# AVCC_3.net
KiCad netlist of a schematic drawn in Altium Designer
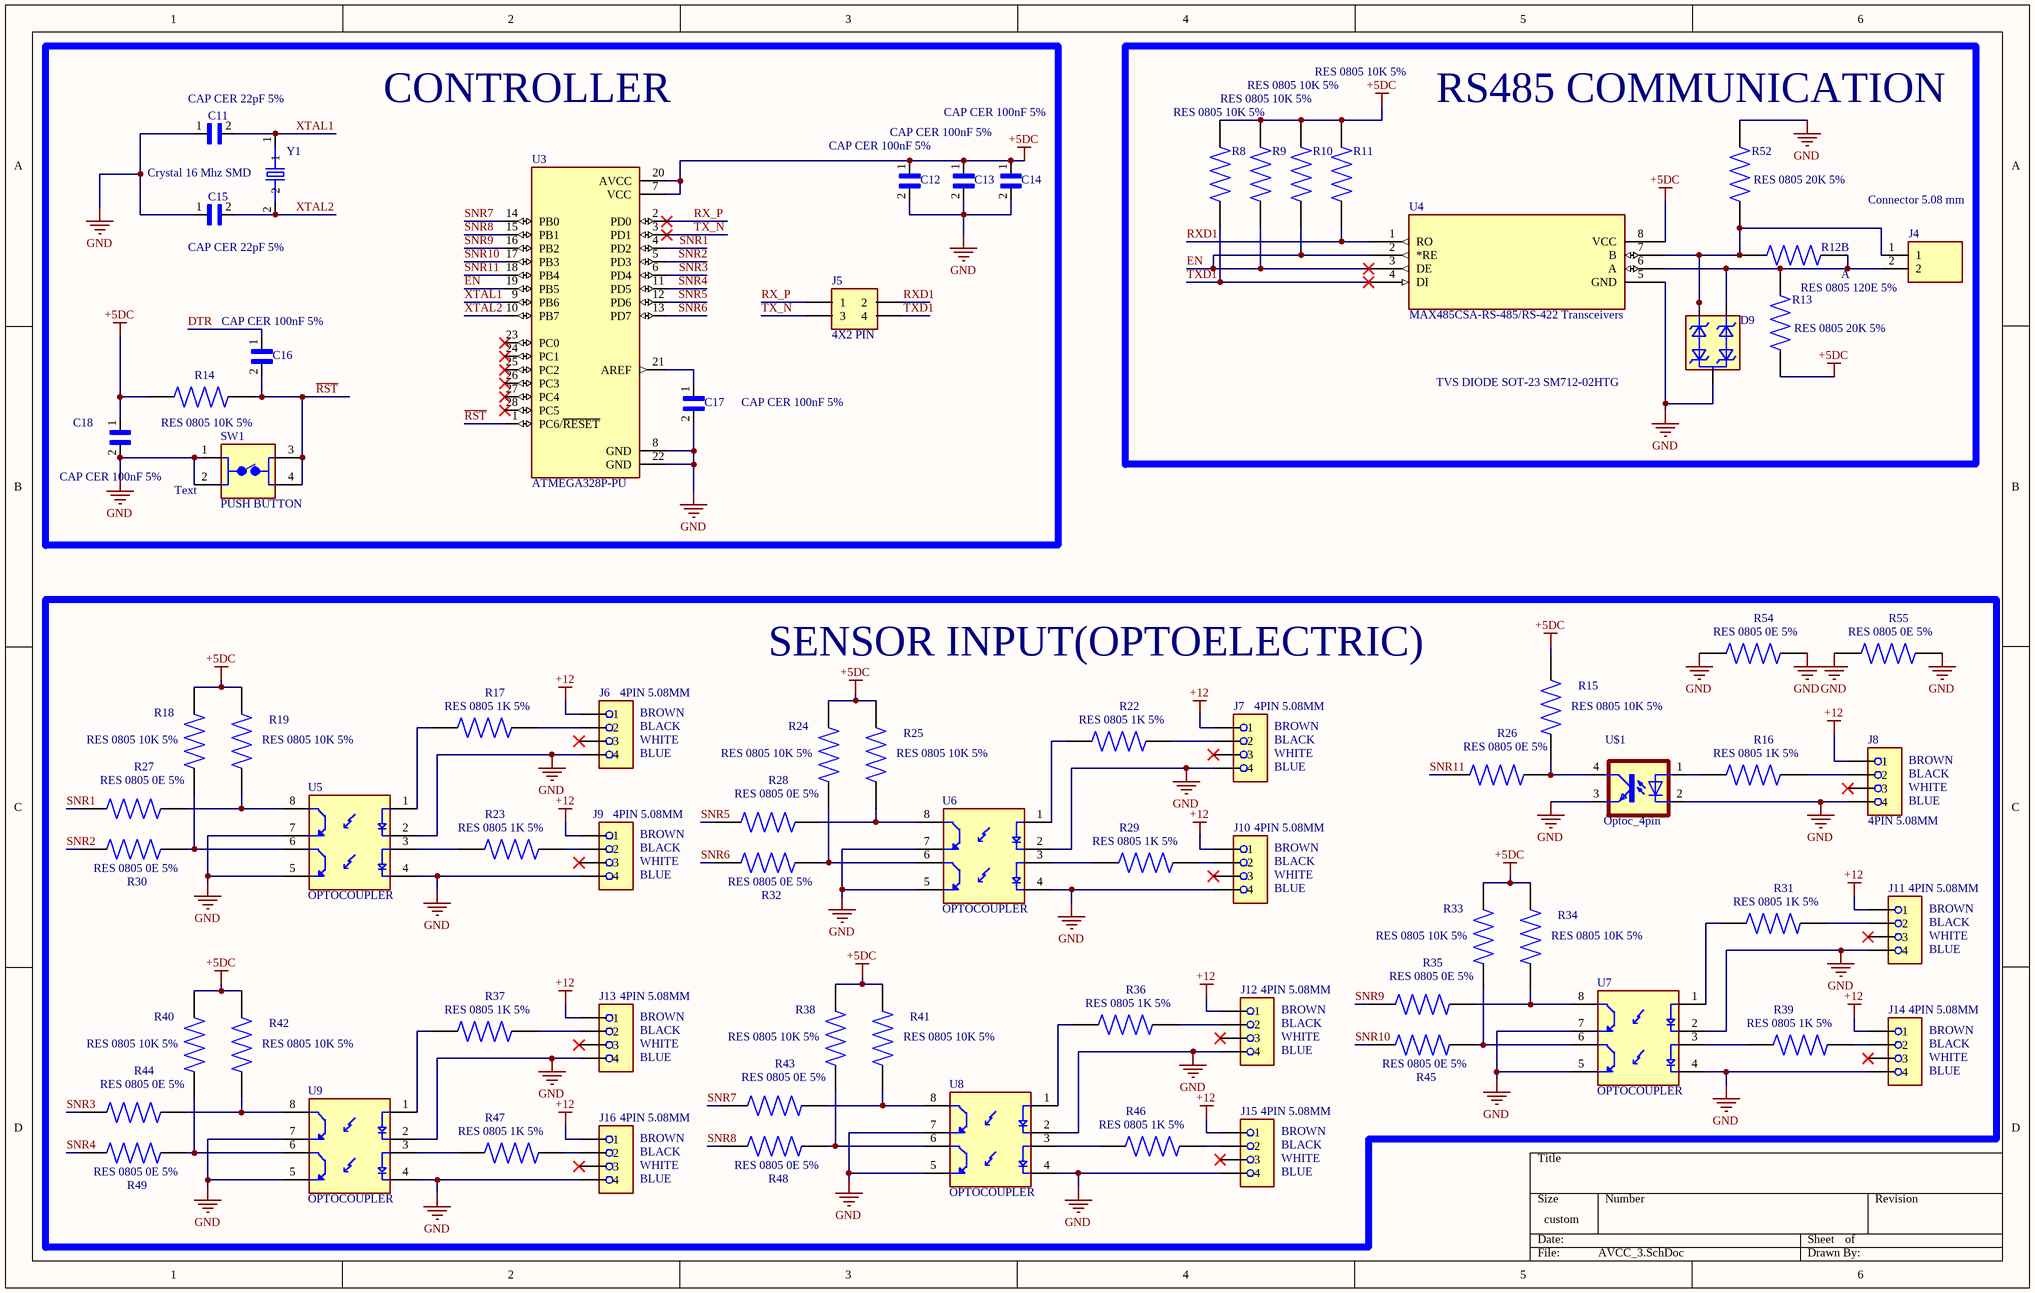
[diagram p0: AVCC_3.SchDoc]

(export (version "E")
  (design (tool "Eeschema 10.0.6"))
  (components
    (comp (ref "C11")
      (value "CAP CER 22pF 5%")
      (footprint "CAP CER 100pF 5%")
      (description "CAP CER 100PF50V X7R 0805")
      (fields (field (name "MP") "GCJ216R71H222KA01D"))
      (libsource (lib "") (part "CAP CER 100pF 5%_1"))
    )
    (comp (ref "C12")
      (value "CAP CER 100nF 5%")
      (footprint "CAP CER 100pF 5%")
      (description "CAP CER 100PF50V X7R 0805")
      (fields (field (name "MP") "GCJ216R71H222KA01D"))
      (libsource (lib "RS485_SCH_Lib") (part "CAP CER 100pF 5%"))
    )
    (comp (ref "C13")
      (value "CAP CER 100nF 5%")
      (footprint "CAP CER 100pF 5%")
      (description "CAP CER 100PF50V X7R 0805")
      (fields (field (name "MP") "GCJ216R71H222KA01D"))
      (libsource (lib "RS485_SCH_Lib") (part "CAP CER 100pF 5%"))
    )
    (comp (ref "C14")
      (value "CAP CER 100nF 5%")
      (footprint "CAP CER 100pF 5%")
      (description "CAP CER 100PF50V X7R 0805")
      (fields (field (name "MP") "GCJ216R71H222KA01D"))
      (libsource (lib "RS485_SCH_Lib") (part "CAP CER 100pF 5%"))
    )
    (comp (ref "C15")
      (value "CAP CER 22pF 5%")
      (footprint "CAP CER 100pF 5%")
      (description "CAP CER 100PF50V X7R 0805")
      (fields (field (name "MP") "GCJ216R71H222KA01D"))
      (libsource (lib "") (part "CAP CER 100pF 5%_1"))
    )
    (comp (ref "C16")
      (value "CAP CER 100nF 5%")
      (footprint "CAP CER 100pF 5%")
      (description "CAP CER 100PF50V X7R 0805")
      (fields (field (name "MP") "GCJ216R71H222KA01D"))
      (libsource (lib "RS485_SCH_Lib") (part "CAP CER 100pF 5%"))
    )
    (comp (ref "C17")
      (value "CAP CER 100nF 5%")
      (footprint "CAP CER 100pF 5%")
      (description "CAP CER 100PF50V X7R 0805")
      (fields (field (name "MP") "GCJ216R71H222KA01D"))
      (libsource (lib "RS485_SCH_Lib") (part "CAP CER 100pF 5%"))
    )
    (comp (ref "C18")
      (value "CAP CER 100nF 5%")
      (footprint "CAP CER 100pF 5%")
      (description "CAP CER 100PF50V X7R 0805")
      (fields (field (name "MP") "GCJ216R71H222KA01D"))
      (libsource (lib "RS485_SCH_Lib") (part "CAP CER 100pF 5%"))
    )
    (comp (ref "D9")
      (value "TVS DIODE SOT-23 SM712-02HTG")
      (footprint "TVS Diode SOT23")
      (fields (field (name "MF") "Littelfuse Inc.") (field (name "MP") "SM712-02HTG"))
      (libsource (lib "RS485_SCH_Lib") (part "TVS DIODE SOT-23 SM712-02HTG"))
    )
    (comp (ref "J4")
      (value "Connector 5.08 mm")
      (footprint "Connector 5.08 mm")
      (description "MOLEX,Screw Type, Horizontal, 5.08 Pitch, 24~12 (AWG), Terminal Block Connector")
      (fields (field (name "MF") "Same Sky") (field (name "MP") "TB007-508-02BE"))
      (libsource (lib "RS485_SCH_Lib") (part "Connector 5.08 mm"))
    )
    (comp (ref "J5")
      (value "4X2 PIN")
      (footprint "4PIN BURGE")
      (description "Connector Header Through Hole 4 position 0.100 (2.54mm), 4X2 PIN")
      (fields (field (name "MF") "Samtec") (field (name "MP") "MTLW-102-05-G-D-180"))
      (libsource (lib "RS485_SCH_Lib") (part "4PIN BURGE"))
    )
    (comp (ref "J6")
      (value "4PIN 5.08MM")
      (footprint "TERMINSL SCREW")
      (description "TERMINSL SCREW, 4PIN, 5.08MM")
      (fields (field (name "MF") "{'manufacturer': u'Phoenix Contact'}") (field (name "MP") "1995664"))
      (libsource (lib "RS485_SCH_Lib") (part "TERMINSL SCREW"))
    )
    (comp (ref "J7")
      (value "4PIN 5.08MM")
      (footprint "TERMINSL SCREW")
      (description "TERMINSL SCREW, 4PIN, 5.08MM")
      (fields (field (name "MF") "{'manufacturer': u'Phoenix Contact'}") (field (name "MP") "1995664"))
      (libsource (lib "RS485_SCH_Lib") (part "TERMINSL SCREW"))
    )
    (comp (ref "J8")
      (value "4PIN 5.08MM")
      (footprint "TERMINSL SCREW")
      (description "TERMINSL SCREW, 4PIN, 5.08MM")
      (fields (field (name "MF") "{'manufacturer': u'Phoenix Contact'}") (field (name "MP") "1995664"))
      (libsource (lib "RS485_SCH_Lib") (part "TERMINSL SCREW"))
    )
    (comp (ref "J9")
      (value "4PIN 5.08MM")
      (footprint "TERMINSL SCREW")
      (description "TERMINSL SCREW, 4PIN, 5.08MM")
      (fields (field (name "MF") "{'manufacturer': u'Phoenix Contact'}") (field (name "MP") "1995664"))
      (libsource (lib "RS485_SCH_Lib") (part "TERMINSL SCREW"))
    )
    (comp (ref "J10")
      (value "4PIN 5.08MM")
      (footprint "TERMINSL SCREW")
      (description "TERMINSL SCREW, 4PIN, 5.08MM")
      (fields (field (name "MF") "{'manufacturer': u'Phoenix Contact'}") (field (name "MP") "1995664"))
      (libsource (lib "RS485_SCH_Lib") (part "TERMINSL SCREW"))
    )
    (comp (ref "J11")
      (value "4PIN 5.08MM")
      (footprint "TERMINSL SCREW")
      (description "TERMINSL SCREW, 4PIN, 5.08MM")
      (fields (field (name "MF") "{'manufacturer': u'Phoenix Contact'}") (field (name "MP") "1995664"))
      (libsource (lib "RS485_SCH_Lib") (part "TERMINSL SCREW"))
    )
    (comp (ref "J12")
      (value "4PIN 5.08MM")
      (footprint "TERMINSL SCREW")
      (description "TERMINSL SCREW, 4PIN, 5.08MM")
      (fields (field (name "MF") "{'manufacturer': u'Phoenix Contact'}") (field (name "MP") "1995664"))
      (libsource (lib "RS485_SCH_Lib") (part "TERMINSL SCREW"))
    )
    (comp (ref "J13")
      (value "4PIN 5.08MM")
      (footprint "TERMINSL SCREW")
      (description "TERMINSL SCREW, 4PIN, 5.08MM")
      (fields (field (name "MF") "{'manufacturer': u'Phoenix Contact'}") (field (name "MP") "1995664"))
      (libsource (lib "RS485_SCH_Lib") (part "TERMINSL SCREW"))
    )
    (comp (ref "J14")
      (value "4PIN 5.08MM")
      (footprint "TERMINSL SCREW")
      (description "TERMINSL SCREW, 4PIN, 5.08MM")
      (fields (field (name "MF") "{'manufacturer': u'Phoenix Contact'}") (field (name "MP") "1995664"))
      (libsource (lib "RS485_SCH_Lib") (part "TERMINSL SCREW"))
    )
    (comp (ref "J15")
      (value "4PIN 5.08MM")
      (footprint "TERMINSL SCREW")
      (description "TERMINSL SCREW, 4PIN, 5.08MM")
      (fields (field (name "MF") "{'manufacturer': u'Phoenix Contact'}") (field (name "MP") "1995664"))
      (libsource (lib "RS485_SCH_Lib") (part "TERMINSL SCREW"))
    )
    (comp (ref "J16")
      (value "4PIN 5.08MM")
      (footprint "TERMINSL SCREW")
      (description "TERMINSL SCREW, 4PIN, 5.08MM")
      (fields (field (name "MF") "{'manufacturer': u'Phoenix Contact'}") (field (name "MP") "1995664"))
      (libsource (lib "RS485_SCH_Lib") (part "TERMINSL SCREW"))
    )
    (comp (ref "R8")
      (value "RES 0805 10K 5%")
      (footprint "RES 0805 10K 5%")
      (fields (field (name "MP") "ERJ-6GEYJ103V") (field (name "MF") "Panasonic Electronic"))
      (libsource (lib "RS485_SCH_Lib") (part "RES 0805 10K 5%"))
    )
    (comp (ref "R9")
      (value "RES 0805 10K 5%")
      (footprint "RES 0805 10K 5%")
      (fields (field (name "MP") "ERJ-6GEYJ103V") (field (name "MF") "Panasonic Electronic"))
      (libsource (lib "RS485_SCH_Lib") (part "RES 0805 10K 5%"))
    )
    (comp (ref "R10")
      (value "RES 0805 10K 5%")
      (footprint "RES 0805 10K 5%")
      (fields (field (name "MP") "ERJ-6GEYJ103V") (field (name "MF") "Panasonic Electronic"))
      (libsource (lib "RS485_SCH_Lib") (part "RES 0805 10K 5%"))
    )
    (comp (ref "R11")
      (value "RES 0805 10K 5%")
      (footprint "RES 0805 10K 5%")
      (fields (field (name "MP") "ERJ-6GEYJ103V") (field (name "MF") "Panasonic Electronic"))
      (libsource (lib "RS485_SCH_Lib") (part "RES 0805 10K 5%"))
    )
    (comp (ref "R12")
      (value "RES 0805 120E 5%")
      (footprint "RES 0805 10K 5%")
      (fields (field (name "MP") "ERJ-6GEYJ103V") (field (name "MF") "Panasonic Electronic"))
      (libsource (lib "RS485_SCH_Lib") (part "RES 0805 10K 5%"))
    )
    (comp (ref "R13")
      (value "RES 0805 20K 5%")
      (footprint "RES 0805 10K 5%")
      (fields (field (name "MP") "ERJ-6GEYJ103V") (field (name "MF") "Panasonic Electronic"))
      (libsource (lib "RS485_SCH_Lib") (part "RES 0805 10K 5%"))
    )
    (comp (ref "R14")
      (value "RES 0805 10K 5%")
      (footprint "RES 0805 10K 5%")
      (fields (field (name "MP") "ERJ-6GEYJ103V") (field (name "MF") "Panasonic Electronic"))
      (libsource (lib "RS485_SCH_Lib") (part "RES 0805 10K 5%"))
    )
    (comp (ref "R15")
      (value "RES 0805 10K 5%")
      (footprint "RES 0805 10K 5%")
      (fields (field (name "MP") "ERJ-6GEYJ103V") (field (name "MF") "Panasonic Electronic"))
      (libsource (lib "RS485_SCH_Lib") (part "RES 0805 10K 5%"))
    )
    (comp (ref "R16")
      (value "RES 0805 1K 5%")
      (footprint "RES 0805 10K 5%")
      (fields (field (name "MP") "ERJ-6GEYJ103V") (field (name "MF") "Panasonic Electronic"))
      (libsource (lib "RS485_SCH_Lib") (part "RES 0805 10K 5%"))
    )
    (comp (ref "R17")
      (value "RES 0805 1K 5%")
      (footprint "RES 0805 10K 5%")
      (fields (field (name "MP") "ERJ-6GEYJ103V") (field (name "MF") "Panasonic Electronic"))
      (libsource (lib "RS485_SCH_Lib") (part "RES 0805 10K 5%"))
    )
    (comp (ref "R18")
      (value "RES 0805 10K 5%")
      (footprint "RES 0805 10K 5%")
      (fields (field (name "MP") "ERJ-6GEYJ103V") (field (name "MF") "Panasonic Electronic"))
      (libsource (lib "RS485_SCH_Lib") (part "RES 0805 10K 5%"))
    )
    (comp (ref "R19")
      (value "RES 0805 10K 5%")
      (footprint "RES 0805 10K 5%")
      (fields (field (name "MP") "ERJ-6GEYJ103V") (field (name "MF") "Panasonic Electronic"))
      (libsource (lib "RS485_SCH_Lib") (part "RES 0805 10K 5%"))
    )
    (comp (ref "R22")
      (value "RES 0805 1K 5%")
      (footprint "RES 0805 10K 5%")
      (fields (field (name "MP") "ERJ-6GEYJ103V") (field (name "MF") "Panasonic Electronic"))
      (libsource (lib "RS485_SCH_Lib") (part "RES 0805 10K 5%"))
    )
    (comp (ref "R23")
      (value "RES 0805 1K 5%")
      (footprint "RES 0805 10K 5%")
      (fields (field (name "MP") "ERJ-6GEYJ103V") (field (name "MF") "Panasonic Electronic"))
      (libsource (lib "RS485_SCH_Lib") (part "RES 0805 10K 5%"))
    )
    (comp (ref "R24")
      (value "RES 0805 10K 5%")
      (footprint "RES 0805 10K 5%")
      (fields (field (name "MP") "ERJ-6GEYJ103V") (field (name "MF") "Panasonic Electronic"))
      (libsource (lib "RS485_SCH_Lib") (part "RES 0805 10K 5%"))
    )
    (comp (ref "R25")
      (value "RES 0805 10K 5%")
      (footprint "RES 0805 10K 5%")
      (fields (field (name "MP") "ERJ-6GEYJ103V") (field (name "MF") "Panasonic Electronic"))
      (libsource (lib "RS485_SCH_Lib") (part "RES 0805 10K 5%"))
    )
    (comp (ref "R26")
      (value "RES 0805 0E 5%")
      (footprint "RES 0805 10K 5%")
      (fields (field (name "MP") "ERJ-6GEYJ103V") (field (name "MF") "Panasonic Electronic"))
      (libsource (lib "RS485_SCH_Lib") (part "RES 0805 10K 5%"))
    )
    (comp (ref "R27")
      (value "RES 0805 0E 5%")
      (footprint "RES 0805 10K 5%")
      (fields (field (name "MP") "ERJ-6GEYJ103V") (field (name "MF") "Panasonic Electronic"))
      (libsource (lib "RS485_SCH_Lib") (part "RES 0805 10K 5%"))
    )
    (comp (ref "R28")
      (value "RES 0805 0E 5%")
      (footprint "RES 0805 10K 5%")
      (fields (field (name "MP") "ERJ-6GEYJ103V") (field (name "MF") "Panasonic Electronic"))
      (libsource (lib "RS485_SCH_Lib") (part "RES 0805 10K 5%"))
    )
    (comp (ref "R29")
      (value "RES 0805 1K 5%")
      (footprint "RES 0805 10K 5%")
      (fields (field (name "MP") "ERJ-6GEYJ103V") (field (name "MF") "Panasonic Electronic"))
      (libsource (lib "RS485_SCH_Lib") (part "RES 0805 10K 5%"))
    )
    (comp (ref "R30")
      (value "RES 0805 0E 5%")
      (footprint "RES 0805 10K 5%")
      (fields (field (name "MP") "ERJ-6GEYJ103V") (field (name "MF") "Panasonic Electronic"))
      (libsource (lib "RS485_SCH_Lib") (part "RES 0805 10K 5%"))
    )
    (comp (ref "R31")
      (value "RES 0805 1K 5%")
      (footprint "RES 0805 10K 5%")
      (fields (field (name "MP") "ERJ-6GEYJ103V") (field (name "MF") "Panasonic Electronic"))
      (libsource (lib "RS485_SCH_Lib") (part "RES 0805 10K 5%"))
    )
    (comp (ref "R32")
      (value "RES 0805 0E 5%")
      (footprint "RES 0805 10K 5%")
      (fields (field (name "MP") "ERJ-6GEYJ103V") (field (name "MF") "Panasonic Electronic"))
      (libsource (lib "RS485_SCH_Lib") (part "RES 0805 10K 5%"))
    )
    (comp (ref "R33")
      (value "RES 0805 10K 5%")
      (footprint "RES 0805 10K 5%")
      (fields (field (name "MP") "ERJ-6GEYJ103V") (field (name "MF") "Panasonic Electronic"))
      (libsource (lib "RS485_SCH_Lib") (part "RES 0805 10K 5%"))
    )
    (comp (ref "R34")
      (value "RES 0805 10K 5%")
      (footprint "RES 0805 10K 5%")
      (fields (field (name "MP") "ERJ-6GEYJ103V") (field (name "MF") "Panasonic Electronic"))
      (libsource (lib "RS485_SCH_Lib") (part "RES 0805 10K 5%"))
    )
    (comp (ref "R35")
      (value "RES 0805 0E 5%")
      (footprint "RES 0805 10K 5%")
      (fields (field (name "MP") "ERJ-6GEYJ103V") (field (name "MF") "Panasonic Electronic"))
      (libsource (lib "RS485_SCH_Lib") (part "RES 0805 10K 5%"))
    )
    (comp (ref "R36")
      (value "RES 0805 1K 5%")
      (footprint "RES 0805 10K 5%")
      (fields (field (name "MP") "ERJ-6GEYJ103V") (field (name "MF") "Panasonic Electronic"))
      (libsource (lib "RS485_SCH_Lib") (part "RES 0805 10K 5%"))
    )
    (comp (ref "R37")
      (value "RES 0805 1K 5%")
      (footprint "RES 0805 10K 5%")
      (fields (field (name "MP") "ERJ-6GEYJ103V") (field (name "MF") "Panasonic Electronic"))
      (libsource (lib "RS485_SCH_Lib") (part "RES 0805 10K 5%"))
    )
    (comp (ref "R38")
      (value "RES 0805 10K 5%")
      (footprint "RES 0805 10K 5%")
      (fields (field (name "MP") "ERJ-6GEYJ103V") (field (name "MF") "Panasonic Electronic"))
      (libsource (lib "RS485_SCH_Lib") (part "RES 0805 10K 5%"))
    )
    (comp (ref "R39")
      (value "RES 0805 1K 5%")
      (footprint "RES 0805 10K 5%")
      (fields (field (name "MP") "ERJ-6GEYJ103V") (field (name "MF") "Panasonic Electronic"))
      (libsource (lib "RS485_SCH_Lib") (part "RES 0805 10K 5%"))
    )
    (comp (ref "R40")
      (value "RES 0805 10K 5%")
      (footprint "RES 0805 10K 5%")
      (fields (field (name "MP") "ERJ-6GEYJ103V") (field (name "MF") "Panasonic Electronic"))
      (libsource (lib "RS485_SCH_Lib") (part "RES 0805 10K 5%"))
    )
    (comp (ref "R41")
      (value "RES 0805 10K 5%")
      (footprint "RES 0805 10K 5%")
      (fields (field (name "MP") "ERJ-6GEYJ103V") (field (name "MF") "Panasonic Electronic"))
      (libsource (lib "RS485_SCH_Lib") (part "RES 0805 10K 5%"))
    )
    (comp (ref "R42")
      (value "RES 0805 10K 5%")
      (footprint "RES 0805 10K 5%")
      (fields (field (name "MP") "ERJ-6GEYJ103V") (field (name "MF") "Panasonic Electronic"))
      (libsource (lib "RS485_SCH_Lib") (part "RES 0805 10K 5%"))
    )
    (comp (ref "R43")
      (value "RES 0805 0E 5%")
      (footprint "RES 0805 10K 5%")
      (fields (field (name "MP") "ERJ-6GEYJ103V") (field (name "MF") "Panasonic Electronic"))
      (libsource (lib "RS485_SCH_Lib") (part "RES 0805 10K 5%"))
    )
    (comp (ref "R44")
      (value "RES 0805 0E 5%")
      (footprint "RES 0805 10K 5%")
      (fields (field (name "MP") "ERJ-6GEYJ103V") (field (name "MF") "Panasonic Electronic"))
      (libsource (lib "RS485_SCH_Lib") (part "RES 0805 10K 5%"))
    )
    (comp (ref "R45")
      (value "RES 0805 0E 5%")
      (footprint "RES 0805 10K 5%")
      (fields (field (name "MP") "ERJ-6GEYJ103V") (field (name "MF") "Panasonic Electronic"))
      (libsource (lib "RS485_SCH_Lib") (part "RES 0805 10K 5%"))
    )
    (comp (ref "R46")
      (value "RES 0805 1K 5%")
      (footprint "RES 0805 10K 5%")
      (fields (field (name "MP") "ERJ-6GEYJ103V") (field (name "MF") "Panasonic Electronic"))
      (libsource (lib "RS485_SCH_Lib") (part "RES 0805 10K 5%"))
    )
    (comp (ref "R47")
      (value "RES 0805 1K 5%")
      (footprint "RES 0805 10K 5%")
      (fields (field (name "MP") "ERJ-6GEYJ103V") (field (name "MF") "Panasonic Electronic"))
      (libsource (lib "RS485_SCH_Lib") (part "RES 0805 10K 5%"))
    )
    (comp (ref "R48")
      (value "RES 0805 0E 5%")
      (footprint "RES 0805 10K 5%")
      (fields (field (name "MP") "ERJ-6GEYJ103V") (field (name "MF") "Panasonic Electronic"))
      (libsource (lib "RS485_SCH_Lib") (part "RES 0805 10K 5%"))
    )
    (comp (ref "R49")
      (value "RES 0805 0E 5%")
      (footprint "RES 0805 10K 5%")
      (fields (field (name "MP") "ERJ-6GEYJ103V") (field (name "MF") "Panasonic Electronic"))
      (libsource (lib "RS485_SCH_Lib") (part "RES 0805 10K 5%"))
    )
    (comp (ref "R52")
      (value "RES 0805 20K 5%")
      (footprint "RES 0805 10K 5%")
      (fields (field (name "MP") "ERJ-6GEYJ103V") (field (name "MF") "Panasonic Electronic"))
      (libsource (lib "RS485_SCH_Lib") (part "RES 0805 10K 5%"))
    )
    (comp (ref "R54")
      (value "RES 0805 0E 5%")
      (footprint "RES 0805 10K 5%")
      (fields (field (name "MP") "ERJ-6GEYJ103V") (field (name "MF") "Panasonic Electronic"))
      (libsource (lib "RS485_SCH_Lib") (part "RES 0805 10K 5%"))
    )
    (comp (ref "R55")
      (value "RES 0805 0E 5%")
      (footprint "RES 0805 10K 5%")
      (fields (field (name "MP") "ERJ-6GEYJ103V") (field (name "MF") "Panasonic Electronic"))
      (libsource (lib "RS485_SCH_Lib") (part "RES 0805 10K 5%"))
    )
    (comp (ref "SW1")
      (value "PUSH BUTTON")
      (footprint "Push Button")
      (description "Switch Push Button OFF (ON) SPST Round Button 0.05A 24VDC Momentary Contact PC Pins Thru-Hole")
      (fields (field (name "MF") "TE Connectivity") (field (name "MP") "3-1825910-1"))
      (libsource (lib "RS485_SCH_Lib") (part "PUSH BUTTON"))
    )
    (comp (ref "U$1")
      (value "Optoc_4pin")
      (footprint "Optoisolator")
      (description "TLP521-1,Optoisolator Transistor Output 5300Vrms 1 Channel 4-DIP")
      (fields (field (name "MF") "Isocom") (field (name "MP") "TLP521-1"))
      (libsource (lib "RS485_SCH_Lib") (part "Optoc_4pin"))
    )
    (comp (ref "U3")
      (value "ATMEGA328P-PU")
      (footprint "ATMEGA328P DIP28")
      (description "ATmega Series 20 MHz 32 KB Flash 2 KB SRAM 8-Bit Microcontroller - DIP-28")
      (libsource (lib "RS485_SCH_Lib") (part "ATMEGA328P-PU"))
    )
    (comp (ref "U4")
      (value "MAX485CSA-RS-485/RS-422 Transceivers")
      (footprint "MAX485CSA-RS-485/RS-422 Transceivers")
      (description "Low-Power, Slew-Rate-Limited RS-485/RS-422 Transceivers")
      (fields (field (name "MF") "Analog Devices") (field (name "MP") "MAX485CSA+"))
      (libsource (lib "RS485_SCH_Lib") (part "MAX485CSA-RS-485/RS-422 Transceivers"))
    )
    (comp (ref "U5")
      (value "OPTOCOUPLER")
      (footprint "OPTOCOUPLER")
      (description "TLP521-2,Optoisolateur Ã  sortie transistor 5300 Vrms 2 canaux 8 DIP")
      (fields (field (name "MF") "Toshiba") (field (name "MP") "TLP521-2"))
      (libsource (lib "RS485_SCH_Lib") (part "OPTOCOUPLER"))
    )
    (comp (ref "U6")
      (value "OPTOCOUPLER")
      (footprint "OPTOCOUPLER")
      (description "TLP521-2,Optoisolateur Ã  sortie transistor 5300 Vrms 2 canaux 8 DIP")
      (fields (field (name "MF") "Toshiba") (field (name "MP") "TLP521-2"))
      (libsource (lib "RS485_SCH_Lib") (part "OPTOCOUPLER"))
    )
    (comp (ref "U7")
      (value "OPTOCOUPLER")
      (footprint "OPTOCOUPLER")
      (description "TLP521-2,Optoisolateur Ã  sortie transistor 5300 Vrms 2 canaux 8 DIP")
      (fields (field (name "MF") "Toshiba") (field (name "MP") "TLP521-2"))
      (libsource (lib "RS485_SCH_Lib") (part "OPTOCOUPLER"))
    )
    (comp (ref "U8")
      (value "OPTOCOUPLER")
      (footprint "OPTOCOUPLER")
      (description "TLP521-2,Optoisolateur Ã  sortie transistor 5300 Vrms 2 canaux 8 DIP")
      (fields (field (name "MF") "Toshiba") (field (name "MP") "TLP521-2"))
      (libsource (lib "RS485_SCH_Lib") (part "OPTOCOUPLER"))
    )
    (comp (ref "U9")
      (value "OPTOCOUPLER")
      (footprint "OPTOCOUPLER")
      (description "TLP521-2,Optoisolateur Ã  sortie transistor 5300 Vrms 2 canaux 8 DIP")
      (fields (field (name "MF") "Toshiba") (field (name "MP") "TLP521-2"))
      (libsource (lib "RS485_SCH_Lib") (part "OPTOCOUPLER"))
    )
    (comp (ref "Y1")
      (value "Crystal 16 Mhz SMD")
      (footprint "Crystal 16 Mhz SMD")
      (description "16 Mhz Crystal SMD –CSM-4ALX(28ALX) 12.5mmX4.85mmX4mm")
      (fields (field (name "MF") "Fox Electronics") (field (name "MP") "FOXSDLF/128-20"))
      (libsource (lib "RS485_SCH_Lib") (part "Crystal 16 Mhz SMD"))
    )
  )
  (nets
    (net (code "1") (name "+5DC") (class "Default")
      (node (ref "C12") (pin "1") (pinfunction "1_1") (pintype "passive"))
      (node (ref "C13") (pin "1") (pinfunction "1_1") (pintype "passive"))
      (node (ref "C14") (pin "1") (pinfunction "1_1") (pintype "passive"))
      (node (ref "C18") (pin "1") (pinfunction "1_1") (pintype "passive"))
      (node (ref "R10") (pin "2") (pinfunction "2_2") (pintype "passive"))
      (node (ref "R11") (pin "2") (pinfunction "2_2") (pintype "passive"))
      (node (ref "R13") (pin "1") (pinfunction "1_1") (pintype "passive"))
      (node (ref "R14") (pin "1") (pinfunction "1_1") (pintype "passive"))
      (node (ref "R15") (pin "2") (pinfunction "2_2") (pintype "passive"))
      (node (ref "R18") (pin "2") (pinfunction "2_2") (pintype "passive"))
      (node (ref "R19") (pin "2") (pinfunction "2_2") (pintype "passive"))
      (node (ref "R24") (pin "2") (pinfunction "2_2") (pintype "passive"))
      (node (ref "R25") (pin "2") (pinfunction "2_2") (pintype "passive"))
      (node (ref "R33") (pin "2") (pinfunction "2_2") (pintype "passive"))
      (node (ref "R34") (pin "2") (pinfunction "2_2") (pintype "passive"))
      (node (ref "R38") (pin "2") (pinfunction "2_2") (pintype "passive"))
      (node (ref "R40") (pin "2") (pinfunction "2_2") (pintype "passive"))
      (node (ref "R41") (pin "2") (pinfunction "2_2") (pintype "passive"))
      (node (ref "R42") (pin "2") (pinfunction "2_2") (pintype "passive"))
      (node (ref "R8") (pin "2") (pinfunction "2_2") (pintype "passive"))
      (node (ref "R9") (pin "2") (pinfunction "2_2") (pintype "passive"))
      (node (ref "U3") (pin "20") (pinfunction "AVCC_20") (pintype "power_in"))
      (node (ref "U3") (pin "7") (pinfunction "VCC_7") (pintype "power_in"))
      (node (ref "U4") (pin "8") (pinfunction "VCC_8") (pintype "power_in"))
    )
    (net (code "2") (name "+12") (class "Default")
      (node (ref "J10") (pin "1") (pinfunction "1_1") (pintype "passive"))
      (node (ref "J11") (pin "1") (pinfunction "1_1") (pintype "passive"))
      (node (ref "J12") (pin "1") (pinfunction "1_1") (pintype "passive"))
      (node (ref "J13") (pin "1") (pinfunction "1_1") (pintype "passive"))
      (node (ref "J14") (pin "1") (pinfunction "1_1") (pintype "passive"))
      (node (ref "J15") (pin "1") (pinfunction "1_1") (pintype "passive"))
      (node (ref "J16") (pin "1") (pinfunction "1_1") (pintype "passive"))
      (node (ref "J6") (pin "1") (pinfunction "1_1") (pintype "passive"))
      (node (ref "J7") (pin "1") (pinfunction "1_1") (pintype "passive"))
      (node (ref "J8") (pin "1") (pinfunction "1_1") (pintype "passive"))
      (node (ref "J9") (pin "1") (pinfunction "1_1") (pintype "passive"))
    )
    (net (code "3") (name "/DTR") (class "Default")
      (node (ref "C16") (pin "1") (pinfunction "1_1") (pintype "passive"))
    )
    (net (code "4") (name "/EN") (class "Default")
      (node (ref "R10") (pin "1") (pinfunction "1_1") (pintype "passive"))
      (node (ref "R9") (pin "1") (pinfunction "1_1") (pintype "passive"))
      (node (ref "U3") (pin "19") (pinfunction "PB5_19") (pintype "bidirectional"))
      (node (ref "U4") (pin "2") (pinfunction "*RE_2") (pintype "output"))
      (node (ref "U4") (pin "3") (pinfunction "DE_3") (pintype "output"))
    )
    (net (code "5") (name "/RXD1") (class "Default")
      (node (ref "J5") (pin "02") (pinfunction "2_02") (pintype "passive"))
      (node (ref "R11") (pin "1") (pinfunction "1_1") (pintype "passive"))
      (node (ref "U4") (pin "1") (pinfunction "RO_1") (pintype "output"))
    )
    (net (code "6") (name "/RX_P") (class "Default")
      (node (ref "J5") (pin "01") (pinfunction "1_01") (pintype "passive"))
      (node (ref "U3") (pin "2") (pinfunction "PD0_2") (pintype "bidirectional"))
    )
    (net (code "7") (name "/SNR1") (class "Default")
      (node (ref "R27") (pin "1") (pinfunction "1_1") (pintype "passive"))
      (node (ref "U3") (pin "4") (pinfunction "PD2_4") (pintype "bidirectional"))
    )
    (net (code "8") (name "/SNR2") (class "Default")
      (node (ref "R30") (pin "1") (pinfunction "1_1") (pintype "passive"))
      (node (ref "U3") (pin "5") (pinfunction "PD3_5") (pintype "bidirectional"))
    )
    (net (code "9") (name "/SNR3") (class "Default")
      (node (ref "R44") (pin "1") (pinfunction "1_1") (pintype "passive"))
      (node (ref "U3") (pin "6") (pinfunction "PD4_6") (pintype "bidirectional"))
    )
    (net (code "10") (name "/SNR4") (class "Default")
      (node (ref "R49") (pin "1") (pinfunction "1_1") (pintype "passive"))
      (node (ref "U3") (pin "11") (pinfunction "PD5_11") (pintype "bidirectional"))
    )
    (net (code "11") (name "/SNR5") (class "Default")
      (node (ref "R28") (pin "1") (pinfunction "1_1") (pintype "passive"))
      (node (ref "U3") (pin "12") (pinfunction "PD6_12") (pintype "bidirectional"))
    )
    (net (code "12") (name "/SNR6") (class "Default")
      (node (ref "R32") (pin "1") (pinfunction "1_1") (pintype "passive"))
      (node (ref "U3") (pin "13") (pinfunction "PD7_13") (pintype "bidirectional"))
    )
    (net (code "13") (name "/SNR7") (class "Default")
      (node (ref "R43") (pin "1") (pinfunction "1_1") (pintype "passive"))
      (node (ref "U3") (pin "14") (pinfunction "PB0_14") (pintype "bidirectional"))
    )
    (net (code "14") (name "/SNR8") (class "Default")
      (node (ref "R48") (pin "1") (pinfunction "1_1") (pintype "passive"))
      (node (ref "U3") (pin "15") (pinfunction "PB1_15") (pintype "bidirectional"))
    )
    (net (code "15") (name "/SNR9") (class "Default")
      (node (ref "R35") (pin "1") (pinfunction "1_1") (pintype "passive"))
      (node (ref "U3") (pin "16") (pinfunction "PB2_16") (pintype "bidirectional"))
    )
    (net (code "16") (name "/SNR10") (class "Default")
      (node (ref "R45") (pin "1") (pinfunction "1_1") (pintype "passive"))
      (node (ref "U3") (pin "17") (pinfunction "PB3_17") (pintype "bidirectional"))
    )
    (net (code "17") (name "/SNR11") (class "Default")
      (node (ref "R26") (pin "1") (pinfunction "1_1") (pintype "passive"))
      (node (ref "U3") (pin "18") (pinfunction "PB4_18") (pintype "bidirectional"))
    )
    (net (code "18") (name "/TXD1") (class "Default")
      (node (ref "J5") (pin "04") (pinfunction "4_04") (pintype "passive"))
      (node (ref "R8") (pin "1") (pinfunction "1_1") (pintype "passive"))
      (node (ref "U4") (pin "4") (pinfunction "DI_4") (pintype "input"))
    )
    (net (code "19") (name "/TX_N") (class "Default")
      (node (ref "J5") (pin "03") (pinfunction "3_03") (pintype "passive"))
      (node (ref "U3") (pin "3") (pinfunction "PD1_3") (pintype "bidirectional"))
    )
    (net (code "20") (name "/XTAL1") (class "Default")
      (node (ref "C11") (pin "2") (pinfunction "2_2") (pintype "passive"))
      (node (ref "U3") (pin "9") (pinfunction "PB6_9") (pintype "bidirectional"))
      (node (ref "Y1") (pin "1") (pinfunction "1_1") (pintype "passive"))
    )
    (net (code "21") (name "/XTAL2") (class "Default")
      (node (ref "C15") (pin "2") (pinfunction "2_2") (pintype "passive"))
      (node (ref "U3") (pin "10") (pinfunction "PB7_10") (pintype "bidirectional"))
      (node (ref "Y1") (pin "2") (pinfunction "2_2") (pintype "passive"))
    )
    (net (code "22") (name "/~{RST}") (class "Default")
      (node (ref "C16") (pin "2") (pinfunction "2_2") (pintype "passive"))
      (node (ref "R14") (pin "2") (pinfunction "2_2") (pintype "passive"))
      (node (ref "SW1") (pin "3") (pinfunction "3_3") (pintype "passive"))
      (node (ref "SW1") (pin "4") (pinfunction "4_4") (pintype "passive"))
      (node (ref "U3") (pin "1") (pinfunction "PC6/~{RESET}_1") (pintype "bidirectional"))
    )
    (net (code "23") (name "GND") (class "Default")
      (node (ref "C11") (pin "1") (pinfunction "1_1") (pintype "passive"))
      (node (ref "C12") (pin "2") (pinfunction "2_2") (pintype "passive"))
      (node (ref "C13") (pin "2") (pinfunction "2_2") (pintype "passive"))
      (node (ref "C14") (pin "2") (pinfunction "2_2") (pintype "passive"))
      (node (ref "C15") (pin "1") (pinfunction "1_1") (pintype "passive"))
      (node (ref "C17") (pin "2") (pinfunction "2_2") (pintype "passive"))
      (node (ref "C18") (pin "2") (pinfunction "2_2") (pintype "passive"))
      (node (ref "D9") (pin "3") (pinfunction "3_3") (pintype "passive"))
      (node (ref "J10") (pin "4") (pinfunction "4_4") (pintype "passive"))
      (node (ref "J11") (pin "4") (pinfunction "4_4") (pintype "passive"))
      (node (ref "J12") (pin "4") (pinfunction "4_4") (pintype "passive"))
      (node (ref "J13") (pin "4") (pinfunction "4_4") (pintype "passive"))
      (node (ref "J14") (pin "4") (pinfunction "4_4") (pintype "passive"))
      (node (ref "J15") (pin "4") (pinfunction "4_4") (pintype "passive"))
      (node (ref "J16") (pin "4") (pinfunction "4_4") (pintype "passive"))
      (node (ref "J6") (pin "4") (pinfunction "4_4") (pintype "passive"))
      (node (ref "J7") (pin "4") (pinfunction "4_4") (pintype "passive"))
      (node (ref "J8") (pin "4") (pinfunction "4_4") (pintype "passive"))
      (node (ref "J9") (pin "4") (pinfunction "4_4") (pintype "passive"))
      (node (ref "R52") (pin "2") (pinfunction "2_2") (pintype "passive"))
      (node (ref "R54") (pin "1") (pinfunction "1_1") (pintype "passive"))
      (node (ref "R54") (pin "2") (pinfunction "2_2") (pintype "passive"))
      (node (ref "R55") (pin "1") (pinfunction "1_1") (pintype "passive"))
      (node (ref "R55") (pin "2") (pinfunction "2_2") (pintype "passive"))
      (node (ref "SW1") (pin "1") (pinfunction "1_1") (pintype "passive"))
      (node (ref "SW1") (pin "2") (pinfunction "2_2") (pintype "passive"))
      (node (ref "U$1") (pin "2") (pinfunction "C_2") (pintype "passive"))
      (node (ref "U$1") (pin "3") (pinfunction "EMIT_3") (pintype "passive"))
      (node (ref "U3") (pin "22") (pinfunction "GND_22") (pintype "power_in"))
      (node (ref "U3") (pin "8") (pinfunction "GND_8") (pintype "power_in"))
      (node (ref "U4") (pin "5") (pinfunction "GND_5") (pintype "power_in"))
      (node (ref "U5") (pin "2") (pinfunction "2_2") (pintype "passive"))
      (node (ref "U5") (pin "4") (pinfunction "4_4") (pintype "passive"))
      (node (ref "U5") (pin "5") (pinfunction "5_5") (pintype "passive"))
      (node (ref "U5") (pin "7") (pinfunction "7_7") (pintype "passive"))
      (node (ref "U6") (pin "2") (pinfunction "2_2") (pintype "passive"))
      (node (ref "U6") (pin "4") (pinfunction "4_4") (pintype "passive"))
      (node (ref "U6") (pin "5") (pinfunction "5_5") (pintype "passive"))
      (node (ref "U6") (pin "7") (pinfunction "7_7") (pintype "passive"))
      (node (ref "U7") (pin "2") (pinfunction "2_2") (pintype "passive"))
      (node (ref "U7") (pin "4") (pinfunction "4_4") (pintype "passive"))
      (node (ref "U7") (pin "5") (pinfunction "5_5") (pintype "passive"))
      (node (ref "U7") (pin "7") (pinfunction "7_7") (pintype "passive"))
      (node (ref "U8") (pin "2") (pinfunction "2_2") (pintype "passive"))
      (node (ref "U8") (pin "4") (pinfunction "4_4") (pintype "passive"))
      (node (ref "U8") (pin "5") (pinfunction "5_5") (pintype "passive"))
      (node (ref "U8") (pin "7") (pinfunction "7_7") (pintype "passive"))
      (node (ref "U9") (pin "2") (pinfunction "2_2") (pintype "passive"))
      (node (ref "U9") (pin "4") (pinfunction "4_4") (pintype "passive"))
      (node (ref "U9") (pin "5") (pinfunction "5_5") (pintype "passive"))
      (node (ref "U9") (pin "7") (pinfunction "7_7") (pintype "passive"))
    )
    (net (code "24") (name "Net-(J6-Pad2)") (class "Default")
      (node (ref "J6") (pin "2") (pinfunction "2_2") (pintype "passive"))
      (node (ref "R17") (pin "1") (pinfunction "1_1") (pintype "passive"))
    )
    (net (code "25") (name "Net-(J7-Pad2)") (class "Default")
      (node (ref "J7") (pin "2") (pinfunction "2_2") (pintype "passive"))
      (node (ref "R22") (pin "1") (pinfunction "1_1") (pintype "passive"))
    )
    (net (code "26") (name "Net-(J8-Pad2)") (class "Default")
      (node (ref "J8") (pin "2") (pinfunction "2_2") (pintype "passive"))
      (node (ref "R16") (pin "1") (pinfunction "1_1") (pintype "passive"))
    )
    (net (code "27") (name "Net-(J9-Pad2)") (class "Default")
      (node (ref "J9") (pin "2") (pinfunction "2_2") (pintype "passive"))
      (node (ref "R23") (pin "1") (pinfunction "1_1") (pintype "passive"))
    )
    (net (code "28") (name "Net-(J10-Pad2)") (class "Default")
      (node (ref "J10") (pin "2") (pinfunction "2_2") (pintype "passive"))
      (node (ref "R29") (pin "1") (pinfunction "1_1") (pintype "passive"))
    )
    (net (code "29") (name "Net-(J11-Pad2)") (class "Default")
      (node (ref "J11") (pin "2") (pinfunction "2_2") (pintype "passive"))
      (node (ref "R31") (pin "1") (pinfunction "1_1") (pintype "passive"))
    )
    (net (code "30") (name "Net-(J12-Pad2)") (class "Default")
      (node (ref "J12") (pin "2") (pinfunction "2_2") (pintype "passive"))
      (node (ref "R36") (pin "1") (pinfunction "1_1") (pintype "passive"))
    )
    (net (code "31") (name "Net-(J13-Pad2)") (class "Default")
      (node (ref "J13") (pin "2") (pinfunction "2_2") (pintype "passive"))
      (node (ref "R37") (pin "1") (pinfunction "1_1") (pintype "passive"))
    )
    (net (code "32") (name "Net-(J14-Pad2)") (class "Default")
      (node (ref "J14") (pin "2") (pinfunction "2_2") (pintype "passive"))
      (node (ref "R39") (pin "1") (pinfunction "1_1") (pintype "passive"))
    )
    (net (code "33") (name "Net-(J15-Pad2)") (class "Default")
      (node (ref "J15") (pin "2") (pinfunction "2_2") (pintype "passive"))
      (node (ref "R46") (pin "1") (pinfunction "1_1") (pintype "passive"))
    )
    (net (code "34") (name "Net-(J16-Pad2)") (class "Default")
      (node (ref "J16") (pin "2") (pinfunction "2_2") (pintype "passive"))
      (node (ref "R47") (pin "1") (pinfunction "1_1") (pintype "passive"))
    )
    (net (code "35") (name "Net-(R17-Pad2)") (class "Default")
      (node (ref "R17") (pin "2") (pinfunction "2_2") (pintype "passive"))
      (node (ref "U5") (pin "1") (pinfunction "1_1") (pintype "passive"))
    )
    (net (code "36") (name "Net-(R18-Pad1)") (class "Default")
      (node (ref "R18") (pin "1") (pinfunction "1_1") (pintype "passive"))
      (node (ref "R30") (pin "2") (pinfunction "2_2") (pintype "passive"))
      (node (ref "U5") (pin "6") (pinfunction "6_6") (pintype "passive"))
    )
    (net (code "37") (name "Net-(R19-Pad1)") (class "Default")
      (node (ref "R19") (pin "1") (pinfunction "1_1") (pintype "passive"))
      (node (ref "R27") (pin "2") (pinfunction "2_2") (pintype "passive"))
      (node (ref "U5") (pin "8") (pinfunction "8_8") (pintype "passive"))
    )
    (net (code "38") (name "Net-(R22-Pad2)") (class "Default")
      (node (ref "R22") (pin "2") (pinfunction "2_2") (pintype "passive"))
      (node (ref "U6") (pin "1") (pinfunction "1_1") (pintype "passive"))
    )
    (net (code "39") (name "Net-(R23-Pad2)") (class "Default")
      (node (ref "R23") (pin "2") (pinfunction "2_2") (pintype "passive"))
      (node (ref "U5") (pin "3") (pinfunction "3_3") (pintype "passive"))
    )
    (net (code "40") (name "Net-(R24-Pad1)") (class "Default")
      (node (ref "R24") (pin "1") (pinfunction "1_1") (pintype "passive"))
      (node (ref "R32") (pin "2") (pinfunction "2_2") (pintype "passive"))
      (node (ref "U6") (pin "6") (pinfunction "6_6") (pintype "passive"))
    )
    (net (code "41") (name "Net-(R25-Pad1)") (class "Default")
      (node (ref "R25") (pin "1") (pinfunction "1_1") (pintype "passive"))
      (node (ref "R28") (pin "2") (pinfunction "2_2") (pintype "passive"))
      (node (ref "U6") (pin "8") (pinfunction "8_8") (pintype "passive"))
    )
    (net (code "42") (name "Net-(R29-Pad2)") (class "Default")
      (node (ref "R29") (pin "2") (pinfunction "2_2") (pintype "passive"))
      (node (ref "U6") (pin "3") (pinfunction "3_3") (pintype "passive"))
    )
    (net (code "43") (name "Net-(R31-Pad2)") (class "Default")
      (node (ref "R31") (pin "2") (pinfunction "2_2") (pintype "passive"))
      (node (ref "U7") (pin "1") (pinfunction "1_1") (pintype "passive"))
    )
    (net (code "44") (name "Net-(R33-Pad1)") (class "Default")
      (node (ref "R33") (pin "1") (pinfunction "1_1") (pintype "passive"))
      (node (ref "R45") (pin "2") (pinfunction "2_2") (pintype "passive"))
      (node (ref "U7") (pin "6") (pinfunction "6_6") (pintype "passive"))
    )
    (net (code "45") (name "Net-(R34-Pad1)") (class "Default")
      (node (ref "R34") (pin "1") (pinfunction "1_1") (pintype "passive"))
      (node (ref "R35") (pin "2") (pinfunction "2_2") (pintype "passive"))
      (node (ref "U7") (pin "8") (pinfunction "8_8") (pintype "passive"))
    )
    (net (code "46") (name "Net-(R36-Pad2)") (class "Default")
      (node (ref "R36") (pin "2") (pinfunction "2_2") (pintype "passive"))
      (node (ref "U8") (pin "1") (pinfunction "1_1") (pintype "passive"))
    )
    (net (code "47") (name "Net-(R37-Pad2)") (class "Default")
      (node (ref "R37") (pin "2") (pinfunction "2_2") (pintype "passive"))
      (node (ref "U9") (pin "1") (pinfunction "1_1") (pintype "passive"))
    )
    (net (code "48") (name "Net-(R38-Pad1)") (class "Default")
      (node (ref "R38") (pin "1") (pinfunction "1_1") (pintype "passive"))
      (node (ref "R48") (pin "2") (pinfunction "2_2") (pintype "passive"))
      (node (ref "U8") (pin "6") (pinfunction "6_6") (pintype "passive"))
    )
    (net (code "49") (name "Net-(R39-Pad2)") (class "Default")
      (node (ref "R39") (pin "2") (pinfunction "2_2") (pintype "passive"))
      (node (ref "U7") (pin "3") (pinfunction "3_3") (pintype "passive"))
    )
    (net (code "50") (name "Net-(R40-Pad1)") (class "Default")
      (node (ref "R40") (pin "1") (pinfunction "1_1") (pintype "passive"))
      (node (ref "R49") (pin "2") (pinfunction "2_2") (pintype "passive"))
      (node (ref "U9") (pin "6") (pinfunction "6_6") (pintype "passive"))
    )
    (net (code "51") (name "Net-(R41-Pad1)") (class "Default")
      (node (ref "R41") (pin "1") (pinfunction "1_1") (pintype "passive"))
      (node (ref "R43") (pin "2") (pinfunction "2_2") (pintype "passive"))
      (node (ref "U8") (pin "8") (pinfunction "8_8") (pintype "passive"))
    )
    (net (code "52") (name "Net-(R42-Pad1)") (class "Default")
      (node (ref "R42") (pin "1") (pinfunction "1_1") (pintype "passive"))
      (node (ref "R44") (pin "2") (pinfunction "2_2") (pintype "passive"))
      (node (ref "U9") (pin "8") (pinfunction "8_8") (pintype "passive"))
    )
    (net (code "53") (name "Net-(R46-Pad2)") (class "Default")
      (node (ref "R46") (pin "2") (pinfunction "2_2") (pintype "passive"))
      (node (ref "U8") (pin "3") (pinfunction "3_3") (pintype "passive"))
    )
    (net (code "54") (name "Net-(R47-Pad2)") (class "Default")
      (node (ref "R47") (pin "2") (pinfunction "2_2") (pintype "passive"))
      (node (ref "U9") (pin "3") (pinfunction "3_3") (pintype "passive"))
    )
    (net (code "55") (name "Net-(U$1-A)") (class "Default")
      (node (ref "R16") (pin "2") (pinfunction "2_2") (pintype "passive"))
      (node (ref "U$1") (pin "1") (pinfunction "A_1") (pintype "passive"))
    )
    (net (code "56") (name "Net-(U$1-COL)") (class "Default")
      (node (ref "R15") (pin "1") (pinfunction "1_1") (pintype "passive"))
      (node (ref "R26") (pin "2") (pinfunction "2_2") (pintype "passive"))
      (node (ref "U$1") (pin "4") (pinfunction "COL_4") (pintype "passive"))
    )
    (net (code "57") (name "Net-(U3-AREF)") (class "Default")
      (node (ref "C17") (pin "1") (pinfunction "1_1") (pintype "passive"))
      (node (ref "U3") (pin "21") (pinfunction "AREF_21") (pintype "output"))
    )
    (net (code "58") (name "Net-(U4-A)") (class "Default")
      (node (ref "D9") (pin "1") (pinfunction "1_1") (pintype "passive"))
      (node (ref "J4") (pin "2") (pinfunction "2_2") (pintype "passive"))
      (node (ref "R12") (pin "2") (pinfunction "2_2") (pintype "passive"))
      (node (ref "R13") (pin "2") (pinfunction "2_2") (pintype "passive"))
      (node (ref "U4") (pin "6") (pinfunction "A_6") (pintype "bidirectional"))
    )
    (net (code "59") (name "Net-(U4-B)") (class "Default")
      (node (ref "D9") (pin "2") (pinfunction "2_2") (pintype "passive"))
      (node (ref "J4") (pin "1") (pinfunction "1_1") (pintype "passive"))
      (node (ref "R12") (pin "1") (pinfunction "1_1") (pintype "passive"))
      (node (ref "R52") (pin "1") (pinfunction "1_1") (pintype "passive"))
      (node (ref "U4") (pin "7") (pinfunction "B_7") (pintype "bidirectional"))
    )
    (net (code "60") (name "unconnected-(J6-Pad3)") (class "Default")
      (node (ref "J6") (pin "3") (pinfunction "3_3") (pintype "passive+no_connect"))
    )
    (net (code "61") (name "unconnected-(J7-Pad3)") (class "Default")
      (node (ref "J7") (pin "3") (pinfunction "3_3") (pintype "passive+no_connect"))
    )
    (net (code "62") (name "unconnected-(J8-Pad3)") (class "Default")
      (node (ref "J8") (pin "3") (pinfunction "3_3") (pintype "passive+no_connect"))
    )
    (net (code "63") (name "unconnected-(J9-Pad3)") (class "Default")
      (node (ref "J9") (pin "3") (pinfunction "3_3") (pintype "passive+no_connect"))
    )
    (net (code "64") (name "unconnected-(J10-Pad3)") (class "Default")
      (node (ref "J10") (pin "3") (pinfunction "3_3") (pintype "passive+no_connect"))
    )
    (net (code "65") (name "unconnected-(J11-Pad3)") (class "Default")
      (node (ref "J11") (pin "3") (pinfunction "3_3") (pintype "passive+no_connect"))
    )
    (net (code "66") (name "unconnected-(J12-Pad3)") (class "Default")
      (node (ref "J12") (pin "3") (pinfunction "3_3") (pintype "passive+no_connect"))
    )
    (net (code "67") (name "unconnected-(J13-Pad3)") (class "Default")
      (node (ref "J13") (pin "3") (pinfunction "3_3") (pintype "passive+no_connect"))
    )
    (net (code "68") (name "unconnected-(J14-Pad3)") (class "Default")
      (node (ref "J14") (pin "3") (pinfunction "3_3") (pintype "passive+no_connect"))
    )
    (net (code "69") (name "unconnected-(J15-Pad3)") (class "Default")
      (node (ref "J15") (pin "3") (pinfunction "3_3") (pintype "passive+no_connect"))
    )
    (net (code "70") (name "unconnected-(J16-Pad3)") (class "Default")
      (node (ref "J16") (pin "3") (pinfunction "3_3") (pintype "passive+no_connect"))
    )
    (net (code "71") (name "unconnected-(U3-PC0-Pad23)") (class "Default")
      (node (ref "U3") (pin "23") (pinfunction "PC0_23") (pintype "bidirectional+no_connect"))
    )
    (net (code "72") (name "unconnected-(U3-PC1-Pad24)") (class "Default")
      (node (ref "U3") (pin "24") (pinfunction "PC1_24") (pintype "bidirectional+no_connect"))
    )
    (net (code "73") (name "unconnected-(U3-PC2-Pad25)") (class "Default")
      (node (ref "U3") (pin "25") (pinfunction "PC2_25") (pintype "bidirectional+no_connect"))
    )
    (net (code "74") (name "unconnected-(U3-PC3-Pad26)") (class "Default")
      (node (ref "U3") (pin "26") (pinfunction "PC3_26") (pintype "bidirectional+no_connect"))
    )
    (net (code "75") (name "unconnected-(U3-PC4-Pad27)") (class "Default")
      (node (ref "U3") (pin "27") (pinfunction "PC4_27") (pintype "bidirectional+no_connect"))
    )
    (net (code "76") (name "unconnected-(U3-PC5-Pad28)") (class "Default")
      (node (ref "U3") (pin "28") (pinfunction "PC5_28") (pintype "bidirectional+no_connect"))
    )
  )
)
